# PCI_short_card_universal_-_32_BIT-7.net
KiCad netlist of a schematic drawn in Altium Designer
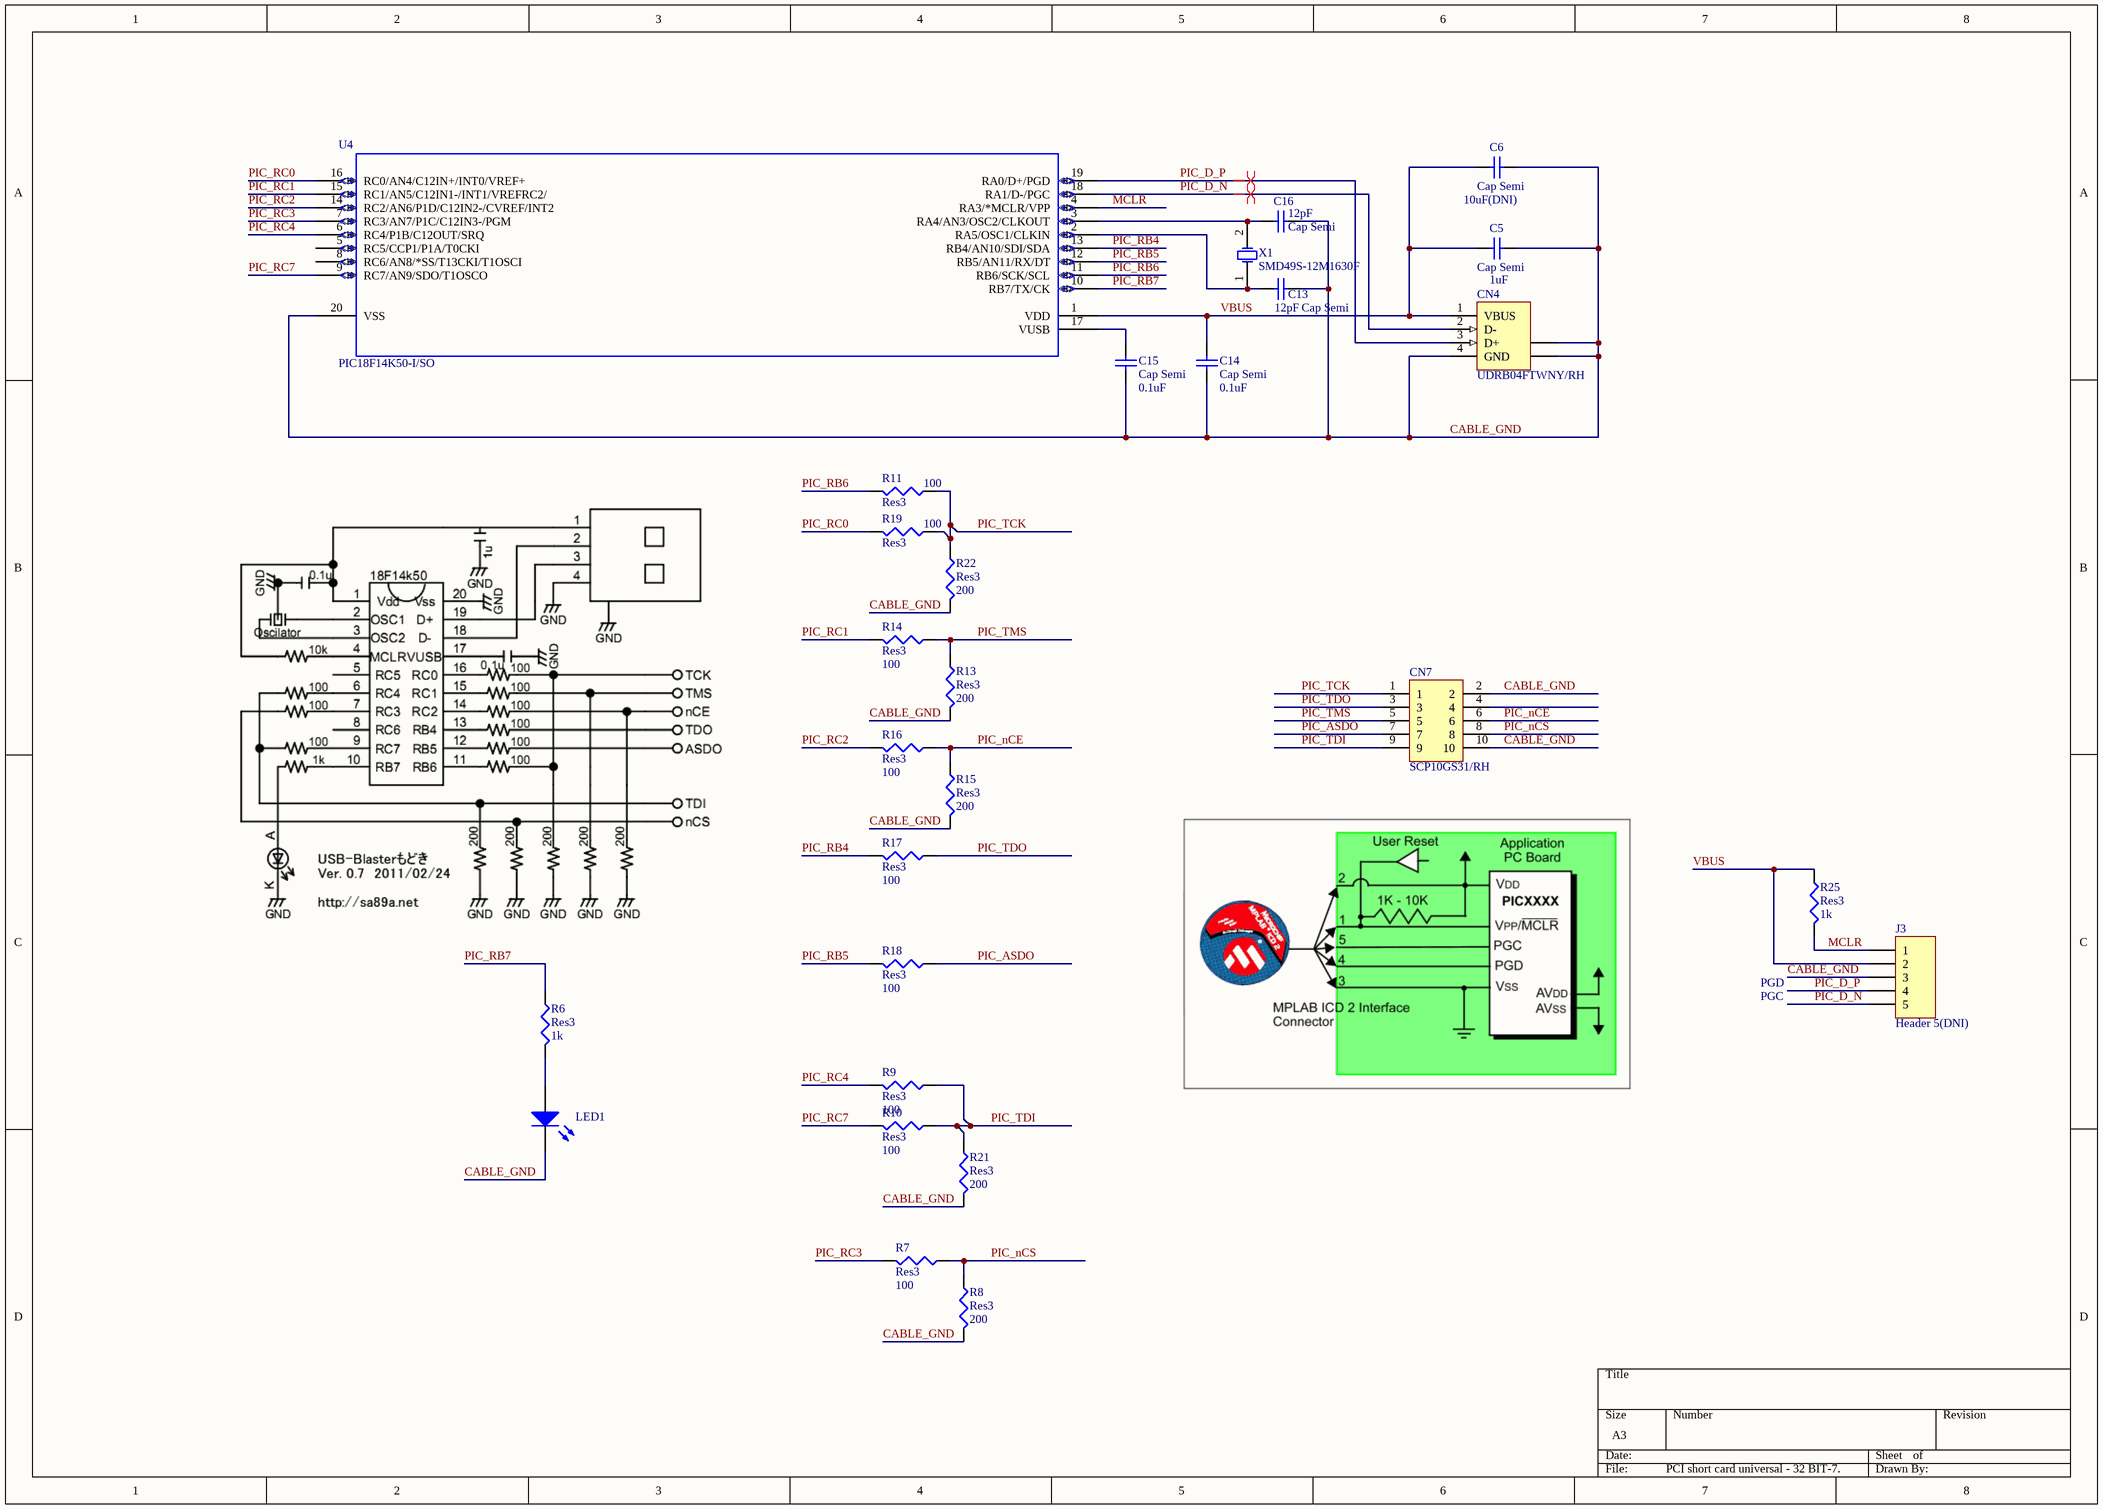
[diagram p0: PCI short card universal - 32 BIT-7.schdoc]

(export (version "E")
  (design (tool "Eeschema 10.0.6"))
  (components
    (comp (ref "C5")
      (value "Cap Semi")
      (footprint "RESC1608N")
      (description "Capacitor (Semiconductor SIM Model)")
      (fields (field (name "ALTIUM_VALUE") "1uF") (field (name "PUBLISHER") "Altium Limited"))
      (libsource (lib "Miscellaneous Devices") (part "Cap Semi"))
    )
    (comp (ref "C6")
      (value "Cap Semi")
      (footprint "RESC2012N")
      (description "Capacitor (Semiconductor SIM Model)")
      (fields (field (name "ALTIUM_VALUE") "10uF(DNI)") (field (name "PUBLISHER") "Altium Limited"))
      (libsource (lib "Miscellaneous Devices") (part "Cap Semi"))
    )
    (comp (ref "C13")
      (value "Cap Semi")
      (footprint "RESC1608N")
      (description "Capacitor (Semiconductor SIM Model)")
      (fields (field (name "ALTIUM_VALUE") "12pF") (field (name "PUBLISHER") "Altium Limited"))
      (libsource (lib "Miscellaneous Devices") (part "Cap Semi"))
    )
    (comp (ref "C14")
      (value "Cap Semi")
      (footprint "RESC1608N")
      (description "Capacitor (Semiconductor SIM Model)")
      (fields (field (name "ALTIUM_VALUE") "0.1uF") (field (name "PUBLISHER") "Altium Limited"))
      (libsource (lib "Miscellaneous Devices") (part "Cap Semi"))
    )
    (comp (ref "C15")
      (value "Cap Semi")
      (footprint "RESC1608N")
      (description "Capacitor (Semiconductor SIM Model)")
      (fields (field (name "ALTIUM_VALUE") "0.1uF") (field (name "PUBLISHER") "Altium Limited"))
      (libsource (lib "Miscellaneous Devices") (part "Cap Semi"))
    )
    (comp (ref "C16")
      (value "Cap Semi")
      (footprint "RESC1608N")
      (description "Capacitor (Semiconductor SIM Model)")
      (fields (field (name "ALTIUM_VALUE") "12pF") (field (name "PUBLISHER") "Altium Limited"))
      (libsource (lib "Miscellaneous Devices") (part "Cap Semi"))
    )
    (comp (ref "CN4")
      (value "UDRB04FTWNY/RH")
      (footprint "1437106")
      (description "GTK")
      (fields (field (name "PUBLISHER") "Altium Limited"))
      (libsource (lib "AMP Serial Bus USB") (part "4-1437106-7"))
    )
    (comp (ref "CN7")
      (value "SCP10GS31/RH")
      (footprint "SCP10GS31/RH")
      (description "GTK")
      (libsource (lib "Schlib1") (part "SCP10GS31/RH"))
    )
    (comp (ref "J3")
      (value "Header 5(DNI)")
      (footprint "HDR1X5")
      (description "Header, 5-Pin")
      (fields (field (name "PUBLISHER") "Altium Limited"))
      (libsource (lib "Miscellaneous Connectors") (part "Header 5"))
    )
    (comp (ref "LED1")
      (value "LED2")
      (footprint "LED3.2X1.6X1.1")
      (description "OASISTEK (TO-3216BC-MAE)")
      (fields (field (name "PUBLISHER") "Altium Limited"))
      (libsource (lib "Miscellaneous Devices") (part "LED2"))
    )
    (comp (ref "R6")
      (value "Res3")
      (footprint "RESC1608N")
      (description "Resistor")
      (fields (field (name "ALTIUM_VALUE") "1k") (field (name "PUBLISHER") "Altium Limited"))
      (libsource (lib "Miscellaneous Devices") (part "Res3"))
    )
    (comp (ref "R7")
      (value "Res3")
      (footprint "RESC1608N")
      (description "Resistor")
      (fields (field (name "ALTIUM_VALUE") "100") (field (name "PUBLISHER") "Altium Limited"))
      (libsource (lib "Miscellaneous Devices") (part "Res3"))
    )
    (comp (ref "R8")
      (value "Res3")
      (footprint "RESC1608N")
      (description "Resistor")
      (fields (field (name "ALTIUM_VALUE") "200") (field (name "PUBLISHER") "Altium Limited"))
      (libsource (lib "Miscellaneous Devices") (part "Res3"))
    )
    (comp (ref "R9")
      (value "Res3")
      (footprint "RESC1608N")
      (description "Resistor")
      (fields (field (name "ALTIUM_VALUE") "100") (field (name "PUBLISHER") "Altium Limited"))
      (libsource (lib "Miscellaneous Devices") (part "Res3"))
    )
    (comp (ref "R10")
      (value "Res3")
      (footprint "RESC1608N")
      (description "Resistor")
      (fields (field (name "ALTIUM_VALUE") "100") (field (name "PUBLISHER") "Altium Limited"))
      (libsource (lib "Miscellaneous Devices") (part "Res3"))
    )
    (comp (ref "R11")
      (value "Res3")
      (footprint "RESC1608N")
      (description "Resistor")
      (fields (field (name "ALTIUM_VALUE") "100") (field (name "PUBLISHER") "Altium Limited"))
      (libsource (lib "Miscellaneous Devices") (part "Res3"))
    )
    (comp (ref "R13")
      (value "Res3")
      (footprint "RESC1608N")
      (description "Resistor")
      (fields (field (name "ALTIUM_VALUE") "200") (field (name "PUBLISHER") "Altium Limited"))
      (libsource (lib "Miscellaneous Devices") (part "Res3"))
    )
    (comp (ref "R14")
      (value "Res3")
      (footprint "RESC1608N")
      (description "Resistor")
      (fields (field (name "ALTIUM_VALUE") "100") (field (name "PUBLISHER") "Altium Limited"))
      (libsource (lib "Miscellaneous Devices") (part "Res3"))
    )
    (comp (ref "R15")
      (value "Res3")
      (footprint "RESC1608N")
      (description "Resistor")
      (fields (field (name "ALTIUM_VALUE") "200") (field (name "PUBLISHER") "Altium Limited"))
      (libsource (lib "Miscellaneous Devices") (part "Res3"))
    )
    (comp (ref "R16")
      (value "Res3")
      (footprint "RESC1608N")
      (description "Resistor")
      (fields (field (name "ALTIUM_VALUE") "100") (field (name "PUBLISHER") "Altium Limited"))
      (libsource (lib "Miscellaneous Devices") (part "Res3"))
    )
    (comp (ref "R17")
      (value "Res3")
      (footprint "RESC1608N")
      (description "Resistor")
      (fields (field (name "ALTIUM_VALUE") "100") (field (name "PUBLISHER") "Altium Limited"))
      (libsource (lib "Miscellaneous Devices") (part "Res3"))
    )
    (comp (ref "R18")
      (value "Res3")
      (footprint "RESC1608N")
      (description "Resistor")
      (fields (field (name "ALTIUM_VALUE") "100") (field (name "PUBLISHER") "Altium Limited"))
      (libsource (lib "Miscellaneous Devices") (part "Res3"))
    )
    (comp (ref "R19")
      (value "Res3")
      (footprint "RESC1608N")
      (description "Resistor")
      (fields (field (name "ALTIUM_VALUE") "100") (field (name "PUBLISHER") "Altium Limited"))
      (libsource (lib "Miscellaneous Devices") (part "Res3"))
    )
    (comp (ref "R21")
      (value "Res3")
      (footprint "RESC1608N")
      (description "Resistor")
      (fields (field (name "ALTIUM_VALUE") "200") (field (name "PUBLISHER") "Altium Limited"))
      (libsource (lib "Miscellaneous Devices") (part "Res3"))
    )
    (comp (ref "R22")
      (value "Res3")
      (footprint "RESC1608N")
      (description "Resistor")
      (fields (field (name "ALTIUM_VALUE") "200") (field (name "PUBLISHER") "Altium Limited"))
      (libsource (lib "Miscellaneous Devices") (part "Res3"))
    )
    (comp (ref "R25")
      (value "Res3")
      (footprint "RESC1608N")
      (description "Resistor")
      (fields (field (name "ALTIUM_VALUE") "1k") (field (name "PUBLISHER") "Altium Limited"))
      (libsource (lib "Miscellaneous Devices") (part "Res3"))
    )
    (comp (ref "U4")
      (value "PIC18F14K50-I/SO")
      (footprint "PIC18F14K50-SO")
      (description "MICROCHIPS")
      (libsource (lib "Schlib1") (part "PIC18F14K50"))
    )
    (comp (ref "X1")
      (value "SMD49S-12M1630F")
      (footprint "ABLS-25.000MHZ-B2F-T")
      (description "MEC")
      (libsource (lib "Schlib1") (part "ABLS-25.000MHZ-B2F-T"))
    )
  )
  (nets
    (net (code "1") (name "/CABLE_GND") (class "Default")
      (node (ref "C13") (pin "1") (pinfunction "1_1") (pintype "passive"))
      (node (ref "C14") (pin "1") (pinfunction "1_1") (pintype "passive"))
      (node (ref "C15") (pin "1") (pinfunction "1_1") (pintype "passive"))
      (node (ref "C16") (pin "1") (pinfunction "1_1") (pintype "passive"))
      (node (ref "C5") (pin "1") (pinfunction "1_1") (pintype "passive"))
      (node (ref "C6") (pin "1") (pinfunction "1_1") (pintype "passive"))
      (node (ref "CN4") (pin "4") (pinfunction "GND_4") (pintype "power_in"))
      (node (ref "CN4") (pin "5") (pinfunction "SHLD_5") (pintype "passive"))
      (node (ref "CN4") (pin "6") (pinfunction "SHLD_6") (pintype "passive"))
      (node (ref "CN7") (pin "10") (pinfunction "10_10") (pintype "passive"))
      (node (ref "CN7") (pin "2") (pinfunction "2_2") (pintype "passive"))
      (node (ref "J3") (pin "3") (pinfunction "3_3") (pintype "passive"))
      (node (ref "LED1") (pin "2") (pinfunction "K_2") (pintype "passive"))
      (node (ref "R13") (pin "2") (pinfunction "2_2") (pintype "passive"))
      (node (ref "R15") (pin "2") (pinfunction "2_2") (pintype "passive"))
      (node (ref "R21") (pin "2") (pinfunction "2_2") (pintype "passive"))
      (node (ref "R22") (pin "2") (pinfunction "2_2") (pintype "passive"))
      (node (ref "R8") (pin "2") (pinfunction "2_2") (pintype "passive"))
      (node (ref "U4") (pin "20") (pinfunction "VSS_20") (pintype "power_in"))
    )
    (net (code "2") (name "/MCLR") (class "Default")
      (node (ref "J3") (pin "1") (pinfunction "1_1") (pintype "passive"))
      (node (ref "R25") (pin "2") (pinfunction "2_2") (pintype "passive"))
      (node (ref "U4") (pin "4") (pinfunction "RA3/*MCLR/VPP_4") (pintype "bidirectional"))
    )
    (net (code "3") (name "/PIC_ASDO") (class "Default")
      (node (ref "CN7") (pin "7") (pinfunction "7_7") (pintype "passive"))
      (node (ref "R18") (pin "1") (pinfunction "1_1") (pintype "passive"))
    )
    (net (code "4") (name "/PIC_D_N") (class "Default")
      (node (ref "CN4") (pin "2") (pinfunction "D-_2") (pintype "input"))
      (node (ref "J3") (pin "5") (pinfunction "5_5") (pintype "passive"))
      (node (ref "U4") (pin "18") (pinfunction "RA1/D-/PGC_18") (pintype "bidirectional"))
    )
    (net (code "5") (name "/PIC_D_P") (class "Default")
      (node (ref "CN4") (pin "3") (pinfunction "D+_3") (pintype "input"))
      (node (ref "J3") (pin "4") (pinfunction "4_4") (pintype "passive"))
      (node (ref "U4") (pin "19") (pinfunction "RA0/D+/PGD_19") (pintype "bidirectional"))
    )
    (net (code "6") (name "/PIC_RB4") (class "Default")
      (node (ref "R17") (pin "2") (pinfunction "2_2") (pintype "passive"))
      (node (ref "U4") (pin "13") (pinfunction "RB4/AN10/SDI/SDA_13") (pintype "bidirectional"))
    )
    (net (code "7") (name "/PIC_RB5") (class "Default")
      (node (ref "R18") (pin "2") (pinfunction "2_2") (pintype "passive"))
      (node (ref "U4") (pin "12") (pinfunction "RB5/AN11/RX/DT_12") (pintype "bidirectional"))
    )
    (net (code "8") (name "/PIC_RB6") (class "Default")
      (node (ref "R11") (pin "2") (pinfunction "2_2") (pintype "passive"))
      (node (ref "U4") (pin "11") (pinfunction "RB6/SCK/SCL_11") (pintype "bidirectional"))
    )
    (net (code "9") (name "/PIC_RB7") (class "Default")
      (node (ref "R6") (pin "1") (pinfunction "1_1") (pintype "passive"))
      (node (ref "U4") (pin "10") (pinfunction "RB7/TX/CK_10") (pintype "bidirectional"))
    )
    (net (code "10") (name "/PIC_RC0") (class "Default")
      (node (ref "R19") (pin "2") (pinfunction "2_2") (pintype "passive"))
      (node (ref "U4") (pin "16") (pinfunction "RC0/AN4/C12IN+/INT0/VREF+_16") (pintype "bidirectional"))
    )
    (net (code "11") (name "/PIC_RC1") (class "Default")
      (node (ref "R14") (pin "2") (pinfunction "2_2") (pintype "passive"))
      (node (ref "U4") (pin "15") (pinfunction "RC1/AN5/C12IN1-/INT1/VREFRC2/_15") (pintype "bidirectional"))
    )
    (net (code "12") (name "/PIC_RC2") (class "Default")
      (node (ref "R16") (pin "2") (pinfunction "2_2") (pintype "passive"))
      (node (ref "U4") (pin "14") (pinfunction "RC2/AN6/P1D/C12IN2-/CVREF/INT2_14") (pintype "bidirectional"))
    )
    (net (code "13") (name "/PIC_RC3") (class "Default")
      (node (ref "R7") (pin "2") (pinfunction "2_2") (pintype "passive"))
      (node (ref "U4") (pin "7") (pinfunction "RC3/AN7/P1C/C12IN3-/PGM_7") (pintype "bidirectional"))
    )
    (net (code "14") (name "/PIC_RC4") (class "Default")
      (node (ref "R9") (pin "2") (pinfunction "2_2") (pintype "passive"))
      (node (ref "U4") (pin "6") (pinfunction "RC4/P1B/C12OUT/SRQ_6") (pintype "bidirectional"))
    )
    (net (code "15") (name "/PIC_RC7") (class "Default")
      (node (ref "R10") (pin "2") (pinfunction "2_2") (pintype "passive"))
      (node (ref "U4") (pin "9") (pinfunction "RC7/AN9/SDO/T1OSCO_9") (pintype "bidirectional"))
    )
    (net (code "16") (name "/PIC_TCK") (class "Default")
      (node (ref "CN7") (pin "1") (pinfunction "1_1") (pintype "passive"))
      (node (ref "R11") (pin "1") (pinfunction "1_1") (pintype "passive"))
      (node (ref "R19") (pin "1") (pinfunction "1_1") (pintype "passive"))
      (node (ref "R22") (pin "1") (pinfunction "1_1") (pintype "passive"))
    )
    (net (code "17") (name "/PIC_TDI") (class "Default")
      (node (ref "CN7") (pin "9") (pinfunction "9_9") (pintype "passive"))
      (node (ref "R10") (pin "1") (pinfunction "1_1") (pintype "passive"))
      (node (ref "R21") (pin "1") (pinfunction "1_1") (pintype "passive"))
      (node (ref "R9") (pin "1") (pinfunction "1_1") (pintype "passive"))
    )
    (net (code "18") (name "/PIC_TDO") (class "Default")
      (node (ref "CN7") (pin "3") (pinfunction "3_3") (pintype "passive"))
      (node (ref "R17") (pin "1") (pinfunction "1_1") (pintype "passive"))
    )
    (net (code "19") (name "/PIC_TMS") (class "Default")
      (node (ref "CN7") (pin "5") (pinfunction "5_5") (pintype "passive"))
      (node (ref "R13") (pin "1") (pinfunction "1_1") (pintype "passive"))
      (node (ref "R14") (pin "1") (pinfunction "1_1") (pintype "passive"))
    )
    (net (code "20") (name "/PIC_nCE") (class "Default")
      (node (ref "CN7") (pin "6") (pinfunction "6_6") (pintype "passive"))
      (node (ref "R15") (pin "1") (pinfunction "1_1") (pintype "passive"))
      (node (ref "R16") (pin "1") (pinfunction "1_1") (pintype "passive"))
    )
    (net (code "21") (name "/PIC_nCS") (class "Default")
      (node (ref "CN7") (pin "8") (pinfunction "8_8") (pintype "passive"))
      (node (ref "R7") (pin "1") (pinfunction "1_1") (pintype "passive"))
      (node (ref "R8") (pin "1") (pinfunction "1_1") (pintype "passive"))
    )
    (net (code "22") (name "/VBUS") (class "Default")
      (node (ref "C14") (pin "2") (pinfunction "2_2") (pintype "passive"))
      (node (ref "C5") (pin "2") (pinfunction "2_2") (pintype "passive"))
      (node (ref "C6") (pin "2") (pinfunction "2_2") (pintype "passive"))
      (node (ref "CN4") (pin "1") (pinfunction "VBUS_1") (pintype "power_in"))
      (node (ref "J3") (pin "2") (pinfunction "2_2") (pintype "passive"))
      (node (ref "R25") (pin "1") (pinfunction "1_1") (pintype "passive"))
      (node (ref "U4") (pin "1") (pinfunction "VDD_1") (pintype "power_in"))
    )
    (net (code "23") (name "Net-(LED1-A)") (class "Default")
      (node (ref "LED1") (pin "1") (pinfunction "A_1") (pintype "passive"))
      (node (ref "R6") (pin "2") (pinfunction "2_2") (pintype "passive"))
    )
    (net (code "24") (name "Net-(U4-RA4{slash}AN3{slash}OSC2{slash}CLKOUT)") (class "Default")
      (node (ref "C16") (pin "2") (pinfunction "2_2") (pintype "passive"))
      (node (ref "U4") (pin "3") (pinfunction "RA4/AN3/OSC2/CLKOUT_3") (pintype "bidirectional"))
      (node (ref "X1") (pin "2") (pinfunction "OSC2_2") (pintype "passive"))
    )
    (net (code "25") (name "Net-(U4-RA5{slash}OSC1{slash}CLKIN)") (class "Default")
      (node (ref "C13") (pin "2") (pinfunction "2_2") (pintype "passive"))
      (node (ref "U4") (pin "2") (pinfunction "RA5/OSC1/CLKIN_2") (pintype "bidirectional"))
      (node (ref "X1") (pin "1") (pinfunction "OSC1_1") (pintype "passive"))
    )
    (net (code "26") (name "Net-(U4-VUSB)") (class "Default")
      (node (ref "C15") (pin "2") (pinfunction "2_2") (pintype "passive"))
      (node (ref "U4") (pin "17") (pinfunction "VUSB_17") (pintype "power_in"))
    )
    (net (code "27") (name "unconnected-(CN7-Pad4)") (class "Default")
      (node (ref "CN7") (pin "4") (pinfunction "4_4") (pintype "passive"))
    )
    (net (code "28") (name "unconnected-(U4-RC5{slash}CCP1{slash}P1A{slash}T0CKI-Pad5)") (class "Default")
      (node (ref "U4") (pin "5") (pinfunction "RC5/CCP1/P1A/T0CKI_5") (pintype "bidirectional"))
    )
    (net (code "29") (name "unconnected-(U4-RC6{slash}AN8{slash}*SS{slash}T13CKI{slash}T1OSCI-Pad8)") (class "Default")
      (node (ref "U4") (pin "8") (pinfunction "RC6/AN8/*SS/T13CKI/T1OSCI_8") (pintype "bidirectional"))
    )
  )
)
